# power_PCB_board2.net
KiCad netlist of a schematic drawn in EAGLE
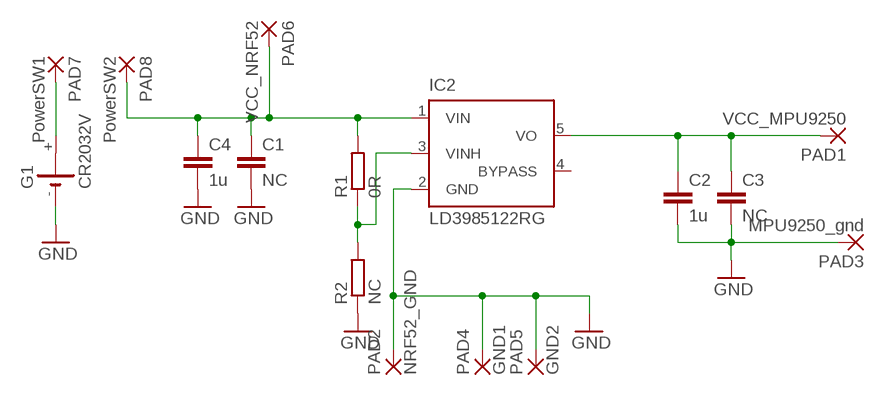
[diagram p0: schematic, sheet 1]

(export (version "E")
  (design (tool "Eeschema 10.0.6"))
  (components
    (comp (ref "C1")
      (value "NC")
      (footprint "eagle-import:C0805")
      (libsource (lib "eagle-import") (part "C-EUC0805"))
    )
    (comp (ref "C2")
      (value "1u")
      (footprint "eagle-import:C0805")
      (libsource (lib "eagle-import") (part "C-EUC0805"))
    )
    (comp (ref "C3")
      (value "NC")
      (footprint "eagle-import:C0805")
      (libsource (lib "eagle-import") (part "C-EUC0805"))
    )
    (comp (ref "C4")
      (value "1u")
      (footprint "eagle-import:C0805")
      (libsource (lib "eagle-import") (part "C-EUC0805"))
    )
    (comp (ref "G1")
      (value "CR2032V")
      (footprint "eagle-import:CR2032V")
      (libsource (lib "eagle-import") (part "CR2032V"))
    )
    (comp (ref "IC2")
      (value "LD3985122RG")
      (footprint "eagle-import:TSOT23-5L")
      (libsource (lib "eagle-import") (part "LD3985G122R"))
    )
    (comp (ref "PAD1")
      (value "VCC_MPU9250")
      (footprint "eagle-import:2,54_1,0")
      (libsource (lib "eagle-import") (part "2,54/1,0"))
    )
    (comp (ref "PAD2")
      (value "NRF52_GND")
      (footprint "eagle-import:2,54_1,0")
      (libsource (lib "eagle-import") (part "2,54/1,0"))
    )
    (comp (ref "PAD3")
      (value "MPU9250_gnd")
      (footprint "eagle-import:2,54_1,0")
      (libsource (lib "eagle-import") (part "2,54/1,0"))
    )
    (comp (ref "PAD4")
      (value "GND1")
      (footprint "eagle-import:2,54_1,0")
      (libsource (lib "eagle-import") (part "2,54/1,0"))
    )
    (comp (ref "PAD5")
      (value "GND2")
      (footprint "eagle-import:2,54_1,0")
      (libsource (lib "eagle-import") (part "2,54/1,0"))
    )
    (comp (ref "PAD6")
      (value "VCC_NRF52")
      (footprint "eagle-import:2,54_1,0")
      (libsource (lib "eagle-import") (part "2,54/1,0"))
    )
    (comp (ref "PAD7")
      (value "PowerSW1")
      (footprint "eagle-import:2,54_1,0")
      (libsource (lib "eagle-import") (part "2,54/1,0"))
    )
    (comp (ref "PAD8")
      (value "PowerSW2")
      (footprint "eagle-import:2,54_1,0")
      (libsource (lib "eagle-import") (part "2,54/1,0"))
    )
    (comp (ref "R1")
      (value "0R")
      (footprint "eagle-import:R0603")
      (libsource (lib "eagle-import") (part "R-EU_R0603"))
    )
    (comp (ref "R2")
      (value "NC")
      (footprint "eagle-import:R0603")
      (libsource (lib "eagle-import") (part "R-EU_R0603"))
    )
  )
  (nets
    (net (code "1") (name "GND") (class "Default")
      (node (ref "C1") (pin "2") (pinfunction "2_2") (pintype "passive"))
      (node (ref "C2") (pin "2") (pinfunction "2_2") (pintype "passive"))
      (node (ref "C3") (pin "2") (pinfunction "2_2") (pintype "passive"))
      (node (ref "C4") (pin "2") (pinfunction "2_2") (pintype "passive"))
      (node (ref "G1") (pin "-") (pinfunction "-_-") (pintype "passive"))
      (node (ref "IC2") (pin "2") (pinfunction "GND_2") (pintype "power_in"))
      (node (ref "PAD2") (pin "1") (pinfunction "P_1") (pintype "passive"))
      (node (ref "PAD3") (pin "1") (pinfunction "P_1") (pintype "passive"))
      (node (ref "PAD4") (pin "1") (pinfunction "P_1") (pintype "passive"))
      (node (ref "PAD5") (pin "1") (pinfunction "P_1") (pintype "passive"))
      (node (ref "R2") (pin "1") (pinfunction "1_1") (pintype "passive"))
    )
    (net (code "2") (name "Net-(IC2-VIN)") (class "Default")
      (node (ref "C1") (pin "1") (pinfunction "1_1") (pintype "passive"))
      (node (ref "C4") (pin "1") (pinfunction "1_1") (pintype "passive"))
      (node (ref "IC2") (pin "1") (pinfunction "VIN_1") (pintype "input"))
      (node (ref "PAD6") (pin "1") (pinfunction "P_1") (pintype "passive"))
      (node (ref "PAD8") (pin "1") (pinfunction "P_1") (pintype "passive"))
      (node (ref "R1") (pin "2") (pinfunction "2_2") (pintype "passive"))
    )
    (net (code "3") (name "Net-(IC2-VINH)") (class "Default")
      (node (ref "IC2") (pin "3") (pinfunction "VINH_3") (pintype "input"))
      (node (ref "R1") (pin "1") (pinfunction "1_1") (pintype "passive"))
      (node (ref "R2") (pin "2") (pinfunction "2_2") (pintype "passive"))
    )
    (net (code "4") (name "Net-(IC2-VO)") (class "Default")
      (node (ref "C2") (pin "1") (pinfunction "1_1") (pintype "passive"))
      (node (ref "C3") (pin "1") (pinfunction "1_1") (pintype "passive"))
      (node (ref "IC2") (pin "5") (pinfunction "VO_5") (pintype "output"))
      (node (ref "PAD1") (pin "1") (pinfunction "P_1") (pintype "passive"))
    )
    (net (code "5") (name "Net-(PAD7-P)") (class "Default")
      (node (ref "G1") (pin "+") (pinfunction "+_+") (pintype "passive"))
      (node (ref "PAD7") (pin "1") (pinfunction "P_1") (pintype "passive"))
    )
    (net (code "6") (name "unconnected-(G1-+-Pad+@1)") (class "Default")
      (node (ref "G1") (pin "+@1") (pinfunction "+_+@1") (pintype "passive"))
    )
    (net (code "7") (name "unconnected-(IC2-BYPASS-Pad4)") (class "Default")
      (node (ref "IC2") (pin "4") (pinfunction "BYPASS_4") (pintype "passive"))
    )
  )
)
